# EDP_and_MIPI_DSI_Connectors.net
KiCad netlist of a schematic drawn in Altium Designer
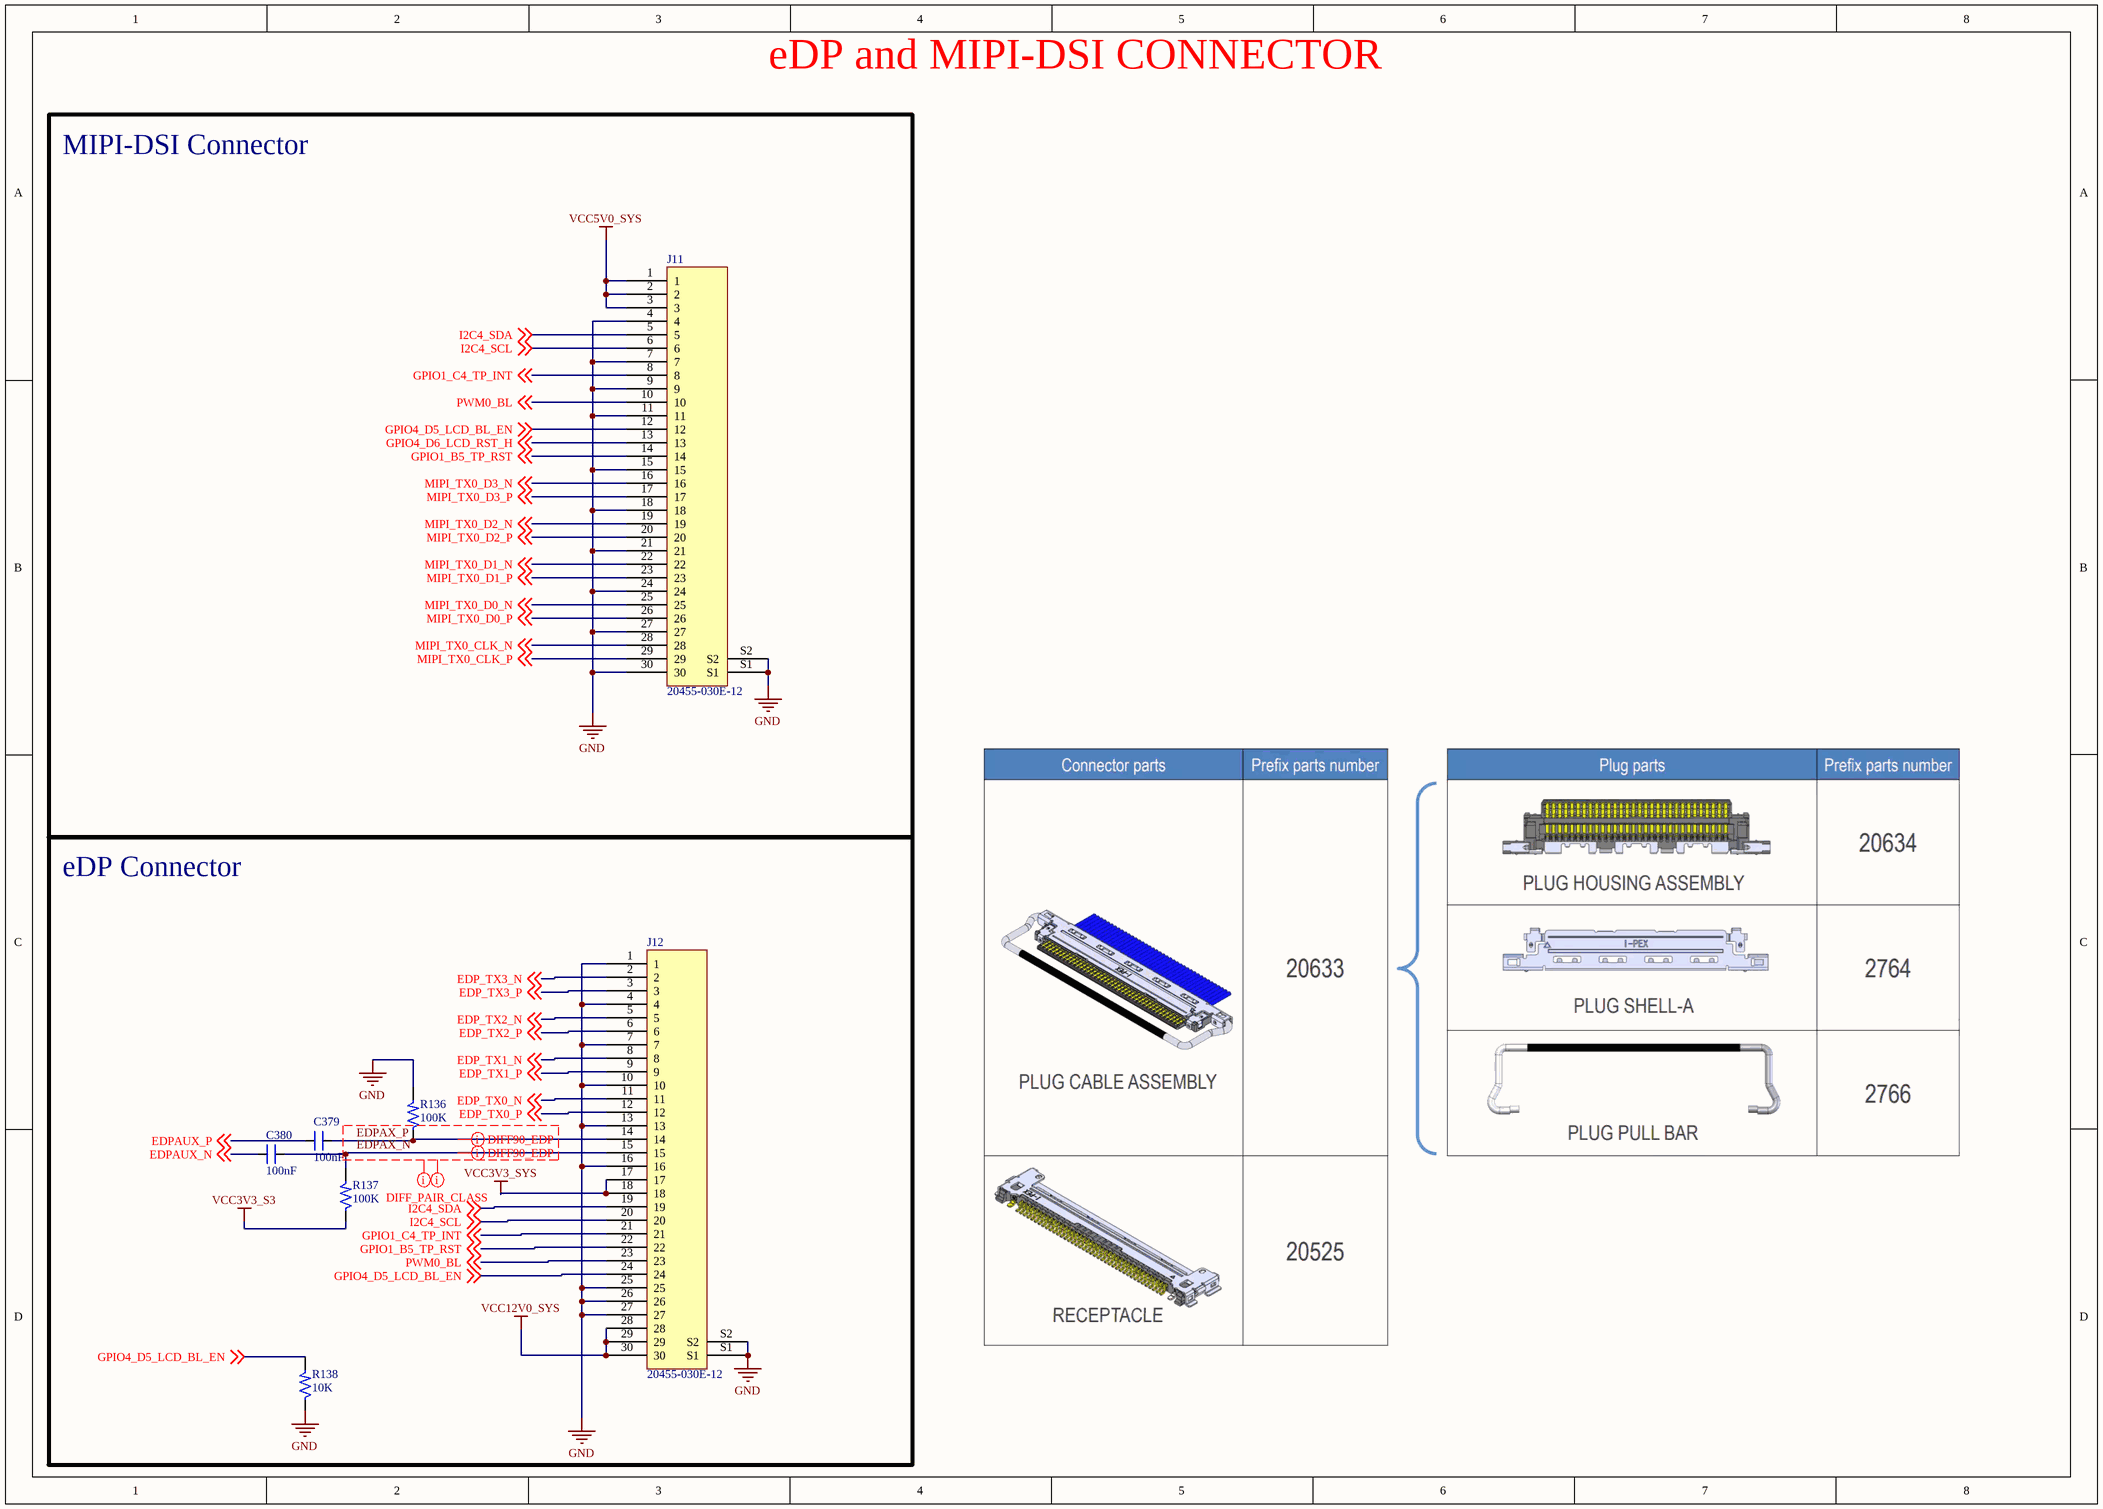
[diagram p0: EDP and MIPI DSI Connectors.SchDoc]

(export (version "E")
  (design (tool "Eeschema 10.0.6"))
  (components
    (comp (ref "C379")
      (value "100nF")
      (footprint "CAP_0402")
      (description "0.1µF ±10% 10V Ceramic Capacitor X7R 0402 (1005 Metric)")
      (fields
        (field (name "MANUFACTURER") "Yageo")
        (field (name "MANUFACTURER PART NUMBER") "CC0402KRX7R6BB104")
      )
      (libsource (lib "RK3399 _Module_Schlib") (part "CAP_100nF-10V-10%-0402"))
    )
    (comp (ref "C380")
      (value "100nF")
      (footprint "CAP_0402")
      (description "0.1µF ±10% 10V Ceramic Capacitor X7R 0402 (1005 Metric)")
      (fields
        (field (name "MANUFACTURER") "Yageo")
        (field (name "MANUFACTURER PART NUMBER") "CC0402KRX7R6BB104")
      )
      (libsource (lib "RK3399 _Module_Schlib") (part "CAP_100nF-10V-10%-0402"))
    )
    (comp (ref "J11")
      (value "20455-030E-12")
      (footprint "CON30_19_68713014522 _SMD_RA")
      (description "Micro Coaxial Connector 0.5mm Pitch")
      (fields
        (field (name "MANUFACTURER") "RS Components")
        (field (name "MATING PART NUMBER") "687730200002")
      )
      (libsource (lib "RK3399 _Module_Intlib") (part "CON-PLG-eDP_30X120455-030E-12-SMD"))
    )
    (comp (ref "J12")
      (value "20455-030E-12")
      (footprint "CON30_19_68713014522 _SMD_RA")
      (description "Micro Coaxial Connector 0.5mm Pitch")
      (fields
        (field (name "MANUFACTURER") "RS Components")
        (field (name "MATING PART NUMBER") "687730200002")
      )
      (libsource (lib "RK3399 _Module_Intlib") (part "CON-PLG-eDP_30X120455-030E-12-SMD"))
    )
    (comp (ref "R136")
      (value "100K")
      (footprint "RES_0603")
      (description "100 kOhms ±1% 0.1W, 1/10W Chip Resistor 0603 (1608 Metric) Automotive AEC-Q200 Thick Film")
      (fields
        (field (name "MANUFACTURER") "tackpole Electronics Inc")
        (field (name "MANUFACTURER PART NUMBER") "RMCF0603FT100K")
      )
      (libsource (lib "RK3399 _Module_Schlib") (part "RES_100K-0.1W-1%-0603"))
    )
    (comp (ref "R137")
      (value "100K")
      (footprint "RES_0603")
      (description "100 kOhms ±1% 0.1W, 1/10W Chip Resistor 0603 (1608 Metric) Automotive AEC-Q200 Thick Film")
      (fields
        (field (name "MANUFACTURER") "tackpole Electronics Inc")
        (field (name "MANUFACTURER PART NUMBER") "RMCF0603FT100K")
      )
      (libsource (lib "RK3399 _Module_Schlib") (part "RES_100K-0.1W-1%-0603"))
    )
    (comp (ref "R138")
      (value "10K")
      (footprint "RES_0603")
      (description "10 kOhms ±1% 0.1W, 1/10W Chip Resistor 0603 (1608 Metric) Thick Film")
      (fields
        (field (name "MANUFACTURER") "Yageo")
        (field (name "MANUFACTURER PART NUMBER") "RC0603FR-0710KL")
      )
      (libsource (lib "RK3399 _Module_Schlib") (part "RES_10K-0.1W-1%-0603"))
    )
  )
  (nets
    (net (code "1") (name "/EDPAX_N") (class "Default")
      (node (ref "C380") (pin "2") (pinfunction "2_2") (pintype "passive"))
      (node (ref "J12") (pin "15") (pinfunction "15_15") (pintype "passive"))
      (node (ref "R137") (pin "2") (pinfunction "2_2") (pintype "passive"))
    )
    (net (code "2") (name "/EDPAX_P") (class "Default")
      (node (ref "C379") (pin "2") (pinfunction "2_2") (pintype "passive"))
      (node (ref "J12") (pin "14") (pinfunction "14_14") (pintype "passive"))
      (node (ref "R136") (pin "1") (pinfunction "1_1") (pintype "passive"))
    )
    (net (code "3") (name "EDPAUX_N") (class "Default")
      (node (ref "C380") (pin "1") (pinfunction "1_1") (pintype "passive"))
    )
    (net (code "4") (name "EDPAUX_P") (class "Default")
      (node (ref "C379") (pin "1") (pinfunction "1_1") (pintype "passive"))
    )
    (net (code "5") (name "EDP_TX0_N") (class "Default")
      (node (ref "J12") (pin "11") (pinfunction "11_11") (pintype "passive"))
    )
    (net (code "6") (name "EDP_TX0_P") (class "Default")
      (node (ref "J12") (pin "12") (pinfunction "12_12") (pintype "passive"))
    )
    (net (code "7") (name "EDP_TX1_N") (class "Default")
      (node (ref "J12") (pin "8") (pinfunction "8_8") (pintype "passive"))
    )
    (net (code "8") (name "EDP_TX1_P") (class "Default")
      (node (ref "J12") (pin "9") (pinfunction "9_9") (pintype "passive"))
    )
    (net (code "9") (name "EDP_TX2_N") (class "Default")
      (node (ref "J12") (pin "5") (pinfunction "5_5") (pintype "passive"))
    )
    (net (code "10") (name "EDP_TX2_P") (class "Default")
      (node (ref "J12") (pin "6") (pinfunction "6_6") (pintype "passive"))
    )
    (net (code "11") (name "EDP_TX3_N") (class "Default")
      (node (ref "J12") (pin "2") (pinfunction "2_2") (pintype "passive"))
    )
    (net (code "12") (name "EDP_TX3_P") (class "Default")
      (node (ref "J12") (pin "3") (pinfunction "3_3") (pintype "passive"))
    )
    (net (code "13") (name "GND") (class "Default")
      (node (ref "J11") (pin "11") (pinfunction "11_11") (pintype "passive"))
      (node (ref "J11") (pin "15") (pinfunction "15_15") (pintype "passive"))
      (node (ref "J11") (pin "18") (pinfunction "18_18") (pintype "passive"))
      (node (ref "J11") (pin "21") (pinfunction "21_21") (pintype "passive"))
      (node (ref "J11") (pin "24") (pinfunction "24_24") (pintype "passive"))
      (node (ref "J11") (pin "27") (pinfunction "27_27") (pintype "passive"))
      (node (ref "J11") (pin "30") (pinfunction "30_30") (pintype "passive"))
      (node (ref "J11") (pin "4") (pinfunction "4_4") (pintype "passive"))
      (node (ref "J11") (pin "7") (pinfunction "7_7") (pintype "passive"))
      (node (ref "J11") (pin "9") (pinfunction "9_9") (pintype "passive"))
      (node (ref "J11") (pin "S1") (pinfunction "S1_S1") (pintype "passive"))
      (node (ref "J11") (pin "S2") (pinfunction "S2_S2") (pintype "passive"))
      (node (ref "J12") (pin "1") (pinfunction "1_1") (pintype "passive"))
      (node (ref "J12") (pin "10") (pinfunction "10_10") (pintype "passive"))
      (node (ref "J12") (pin "13") (pinfunction "13_13") (pintype "passive"))
      (node (ref "J12") (pin "16") (pinfunction "16_16") (pintype "passive"))
      (node (ref "J12") (pin "25") (pinfunction "25_25") (pintype "passive"))
      (node (ref "J12") (pin "26") (pinfunction "26_26") (pintype "passive"))
      (node (ref "J12") (pin "27") (pinfunction "27_27") (pintype "passive"))
      (node (ref "J12") (pin "4") (pinfunction "4_4") (pintype "passive"))
      (node (ref "J12") (pin "7") (pinfunction "7_7") (pintype "passive"))
      (node (ref "J12") (pin "S1") (pinfunction "S1_S1") (pintype "passive"))
      (node (ref "J12") (pin "S2") (pinfunction "S2_S2") (pintype "passive"))
      (node (ref "R136") (pin "2") (pinfunction "2_2") (pintype "passive"))
      (node (ref "R138") (pin "1") (pinfunction "1_1") (pintype "passive"))
    )
    (net (code "14") (name "GPIO1_B5_TP_RST") (class "Default")
      (node (ref "J11") (pin "14") (pinfunction "14_14") (pintype "passive"))
      (node (ref "J12") (pin "22") (pinfunction "22_22") (pintype "passive"))
    )
    (net (code "15") (name "GPIO1_C4_TP_INT") (class "Default")
      (node (ref "J11") (pin "8") (pinfunction "8_8") (pintype "passive"))
      (node (ref "J12") (pin "21") (pinfunction "21_21") (pintype "passive"))
    )
    (net (code "16") (name "GPIO4_D5_LCD_BL_EN") (class "Default")
      (node (ref "J11") (pin "12") (pinfunction "12_12") (pintype "passive"))
      (node (ref "J12") (pin "24") (pinfunction "24_24") (pintype "passive"))
      (node (ref "R138") (pin "2") (pinfunction "2_2") (pintype "passive"))
    )
    (net (code "17") (name "GPIO4_D6_LCD_RST_H") (class "Default")
      (node (ref "J11") (pin "13") (pinfunction "13_13") (pintype "passive"))
    )
    (net (code "18") (name "I2C4_SCL") (class "Default")
      (node (ref "J11") (pin "6") (pinfunction "6_6") (pintype "passive"))
      (node (ref "J12") (pin "20") (pinfunction "20_20") (pintype "passive"))
    )
    (net (code "19") (name "I2C4_SDA") (class "Default")
      (node (ref "J11") (pin "5") (pinfunction "5_5") (pintype "passive"))
      (node (ref "J12") (pin "19") (pinfunction "19_19") (pintype "passive"))
    )
    (net (code "20") (name "MIPI_TX0_CLK_N") (class "Default")
      (node (ref "J11") (pin "28") (pinfunction "28_28") (pintype "passive"))
    )
    (net (code "21") (name "MIPI_TX0_CLK_P") (class "Default")
      (node (ref "J11") (pin "29") (pinfunction "29_29") (pintype "passive"))
    )
    (net (code "22") (name "MIPI_TX0_D0_N") (class "Default")
      (node (ref "J11") (pin "25") (pinfunction "25_25") (pintype "passive"))
    )
    (net (code "23") (name "MIPI_TX0_D0_P") (class "Default")
      (node (ref "J11") (pin "26") (pinfunction "26_26") (pintype "passive"))
    )
    (net (code "24") (name "MIPI_TX0_D1_N") (class "Default")
      (node (ref "J11") (pin "22") (pinfunction "22_22") (pintype "passive"))
    )
    (net (code "25") (name "MIPI_TX0_D1_P") (class "Default")
      (node (ref "J11") (pin "23") (pinfunction "23_23") (pintype "passive"))
    )
    (net (code "26") (name "MIPI_TX0_D2_N") (class "Default")
      (node (ref "J11") (pin "19") (pinfunction "19_19") (pintype "passive"))
    )
    (net (code "27") (name "MIPI_TX0_D2_P") (class "Default")
      (node (ref "J11") (pin "20") (pinfunction "20_20") (pintype "passive"))
    )
    (net (code "28") (name "MIPI_TX0_D3_N") (class "Default")
      (node (ref "J11") (pin "16") (pinfunction "16_16") (pintype "passive"))
    )
    (net (code "29") (name "MIPI_TX0_D3_P") (class "Default")
      (node (ref "J11") (pin "17") (pinfunction "17_17") (pintype "passive"))
    )
    (net (code "30") (name "PWM0_BL") (class "Default")
      (node (ref "J11") (pin "10") (pinfunction "10_10") (pintype "passive"))
      (node (ref "J12") (pin "23") (pinfunction "23_23") (pintype "passive"))
    )
    (net (code "31") (name "VCC3V3_S3") (class "Default")
      (node (ref "R137") (pin "1") (pinfunction "1_1") (pintype "passive"))
    )
    (net (code "32") (name "VCC3V3_SYS") (class "Default")
      (node (ref "J12") (pin "17") (pinfunction "17_17") (pintype "passive"))
      (node (ref "J12") (pin "18") (pinfunction "18_18") (pintype "passive"))
    )
    (net (code "33") (name "VCC5V0_SYS") (class "Default")
      (node (ref "J11") (pin "1") (pinfunction "1_1") (pintype "passive"))
      (node (ref "J11") (pin "2") (pinfunction "2_2") (pintype "passive"))
      (node (ref "J11") (pin "3") (pinfunction "3_3") (pintype "passive"))
    )
    (net (code "34") (name "VCC12V0_SYS") (class "Default")
      (node (ref "J12") (pin "28") (pinfunction "28_28") (pintype "passive"))
      (node (ref "J12") (pin "29") (pinfunction "29_29") (pintype "passive"))
      (node (ref "J12") (pin "30") (pinfunction "30_30") (pintype "passive"))
    )
  )
)
